# hidrosonico_v0-4.net
KiCad netlist of a schematic drawn in EAGLE
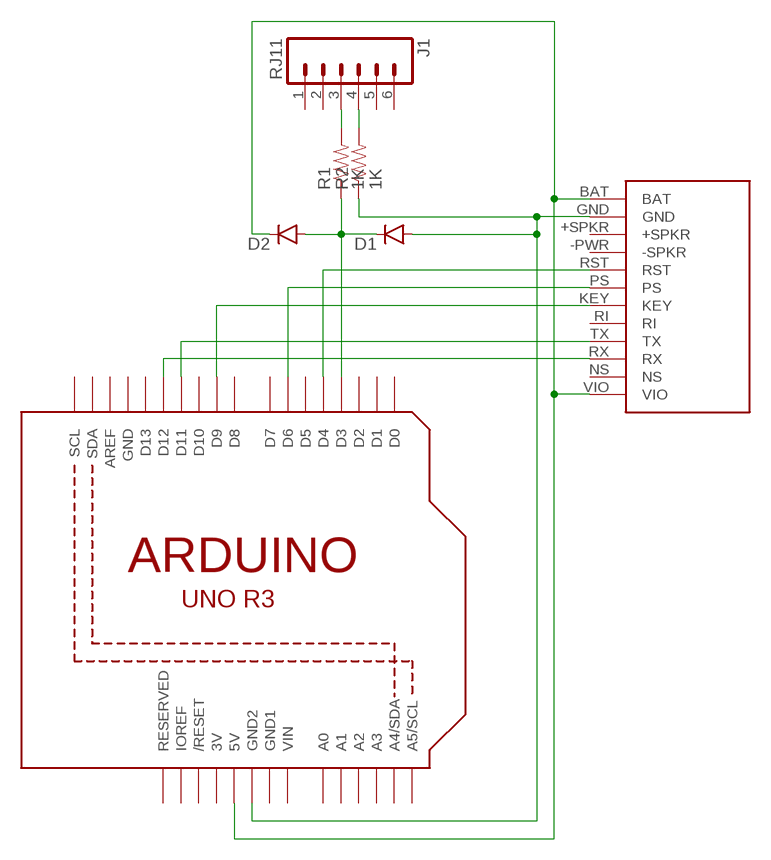
[diagram p0: schematic, sheet 1]

(export (version "E")
  (design (tool "Eeschema 10.0.6"))
  (components
    (comp (ref "D1")
      (value "DIODE1N4148")
      (footprint "eagle-import:DIODE-1N4148")
      (libsource (lib "eagle-import") (part "DIODE1N4148"))
    )
    (comp (ref "D2")
      (value "DIODE1N4148")
      (footprint "eagle-import:DIODE-1N4148")
      (libsource (lib "eagle-import") (part "DIODE1N4148"))
    )
    (comp (ref "J1")
      (value "RJ11")
      (footprint "eagle-import:RJ11-6")
      (libsource (lib "eagle-import") (part "RJ11-6PTH"))
    )
    (comp (ref "R1")
      (value "1K")
      (footprint "eagle-import:AXIAL-0.5")
      (libsource (lib "eagle-import") (part "RESISTORPTH-1/2W"))
    )
    (comp (ref "R2")
      (value "1K")
      (footprint "eagle-import:AXIAL-0.5")
      (libsource (lib "eagle-import") (part "RESISTORPTH-1/2W"))
    )
    (comp (ref "U$1")
      (value "ADAFRUIT_FONA800")
      (footprint "eagle-import:FONA")
      (libsource (lib "eagle-import") (part "ADAFRUIT_FONA800"))
    )
    (comp (ref "U2")
      (value "ARDUINOR3-DIMENSION")
      (footprint "eagle-import:ARDUINOR3")
      (libsource (lib "eagle-import") (part "ARDUINOR3-DIMENSION"))
    )
  )
  (nets
    (net (code "1") (name "/3V") (class "Default")
      (node (ref "U2") (pin "3V") (pinfunction "3V_3V") (pintype "power_in"))
    )
    (net (code "2") (name "/GND") (class "Default")
      (node (ref "U2") (pin "GND") (pinfunction "GND_GND") (pintype "power_in"))
    )
    (net (code "3") (name "/GND1") (class "Default")
      (node (ref "U2") (pin "GND1") (pinfunction "GND1_GND1") (pintype "power_in"))
    )
    (net (code "4") (name "/VIN") (class "Default")
      (node (ref "U2") (pin "VIN") (pinfunction "VIN_VIN") (pintype "power_in"))
    )
    (net (code "5") (name "Net-(D2-PadC)") (class "Default")
      (node (ref "D2") (pin "C") (pinfunction "C_C") (pintype "passive"))
      (node (ref "U$1") (pin "BAT") (pinfunction "BAT_BAT") (pintype "power_in"))
      (node (ref "U$1") (pin "VIO") (pinfunction "VIO_VIO") (pintype "power_in"))
      (node (ref "U2") (pin "5V") (pinfunction "5V_5V") (pintype "power_in"))
    )
    (net (code "6") (name "Net-(R1-1)") (class "Default")
      (node (ref "D1") (pin "C") (pinfunction "C_C") (pintype "passive"))
      (node (ref "D2") (pin "A") (pinfunction "A_A") (pintype "passive"))
      (node (ref "R1") (pin "P$1") (pinfunction "1_P$1") (pintype "passive"))
      (node (ref "U2") (pin "D3") (pinfunction "D3_D3") (pintype "bidirectional"))
    )
    (net (code "7") (name "Net-(R1-2)") (class "Default")
      (node (ref "J1") (pin "3") (pinfunction "3_3") (pintype "passive"))
      (node (ref "R1") (pin "P$2") (pinfunction "2_P$2") (pintype "passive"))
    )
    (net (code "8") (name "Net-(R2-1)") (class "Default")
      (node (ref "D1") (pin "A") (pinfunction "A_A") (pintype "passive"))
      (node (ref "R2") (pin "P$1") (pinfunction "1_P$1") (pintype "passive"))
      (node (ref "U$1") (pin "GND") (pinfunction "GND_GND") (pintype "power_in"))
      (node (ref "U2") (pin "GND2") (pinfunction "GND2_GND2") (pintype "power_in"))
    )
    (net (code "9") (name "Net-(R2-2)") (class "Default")
      (node (ref "J1") (pin "4") (pinfunction "4_4") (pintype "passive"))
      (node (ref "R2") (pin "P$2") (pinfunction "2_P$2") (pintype "passive"))
    )
    (net (code "10") (name "Net-(U$1-PadKEY)") (class "Default")
      (node (ref "U$1") (pin "KEY") (pinfunction "KEY_KEY") (pintype "input"))
      (node (ref "U2") (pin "D9") (pinfunction "D9_D9") (pintype "bidirectional"))
    )
    (net (code "11") (name "Net-(U$1-PadPS)") (class "Default")
      (node (ref "U$1") (pin "PS") (pinfunction "PS_PS") (pintype "output"))
      (node (ref "U2") (pin "D6") (pinfunction "D6_D6") (pintype "bidirectional"))
    )
    (net (code "12") (name "Net-(U$1-PadRST)") (class "Default")
      (node (ref "U$1") (pin "RST") (pinfunction "RST_RST") (pintype "input"))
      (node (ref "U2") (pin "D4") (pinfunction "D4_D4") (pintype "bidirectional"))
    )
    (net (code "13") (name "Net-(U$1-PadRX)") (class "Default")
      (node (ref "U$1") (pin "RX") (pinfunction "RX_RX") (pintype "input"))
      (node (ref "U2") (pin "D12") (pinfunction "D12_D12") (pintype "bidirectional"))
    )
    (net (code "14") (name "Net-(U$1-PadTX)") (class "Default")
      (node (ref "U$1") (pin "TX") (pinfunction "TX_TX") (pintype "output"))
      (node (ref "U2") (pin "D11") (pinfunction "D11_D11") (pintype "bidirectional"))
    )
    (net (code "15") (name "unconnected-(J1-Pad1)") (class "Default")
      (node (ref "J1") (pin "1") (pinfunction "1_1") (pintype "passive"))
    )
    (net (code "16") (name "unconnected-(J1-Pad2)") (class "Default")
      (node (ref "J1") (pin "2") (pinfunction "2_2") (pintype "passive"))
    )
    (net (code "17") (name "unconnected-(J1-Pad5)") (class "Default")
      (node (ref "J1") (pin "5") (pinfunction "5_5") (pintype "passive"))
    )
    (net (code "18") (name "unconnected-(J1-Pad6)") (class "Default")
      (node (ref "J1") (pin "6") (pinfunction "6_6") (pintype "passive"))
    )
    (net (code "19") (name "unconnected-(U$1--SPKR-Pad-PWR)") (class "Default")
      (node (ref "U$1") (pin "-PWR") (pinfunction "-SPKR_-PWR") (pintype "output"))
    )
    (net (code "20") (name "unconnected-(U$1-Pad+SPKR)") (class "Default")
      (node (ref "U$1") (pin "+SPKR") (pinfunction "+SPKR_+SPKR") (pintype "output"))
    )
    (net (code "21") (name "unconnected-(U$1-PadNS)") (class "Default")
      (node (ref "U$1") (pin "NS") (pinfunction "NS_NS") (pintype "output"))
    )
    (net (code "22") (name "unconnected-(U$1-PadRI)") (class "Default")
      (node (ref "U$1") (pin "RI") (pinfunction "RI_RI") (pintype "output"))
    )
    (net (code "23") (name "unconnected-(U2-A4{slash}SDA-PadA4)") (class "Default")
      (node (ref "U2") (pin "A4") (pinfunction "A4/SDA_A4") (pintype "bidirectional"))
    )
    (net (code "24") (name "unconnected-(U2-A5{slash}SCL-PadA5)") (class "Default")
      (node (ref "U2") (pin "A5") (pinfunction "A5/SCL_A5") (pintype "bidirectional"))
    )
    (net (code "25") (name "unconnected-(U2-PadA0)") (class "Default")
      (node (ref "U2") (pin "A0") (pinfunction "A0_A0") (pintype "bidirectional"))
    )
    (net (code "26") (name "unconnected-(U2-PadA1)") (class "Default")
      (node (ref "U2") (pin "A1") (pinfunction "A1_A1") (pintype "bidirectional"))
    )
    (net (code "27") (name "unconnected-(U2-PadA2)") (class "Default")
      (node (ref "U2") (pin "A2") (pinfunction "A2_A2") (pintype "bidirectional"))
    )
    (net (code "28") (name "unconnected-(U2-PadA3)") (class "Default")
      (node (ref "U2") (pin "A3") (pinfunction "A3_A3") (pintype "bidirectional"))
    )
    (net (code "29") (name "unconnected-(U2-PadAREF)") (class "Default")
      (node (ref "U2") (pin "AREF") (pinfunction "AREF_AREF") (pintype "bidirectional"))
    )
    (net (code "30") (name "unconnected-(U2-PadD0)") (class "Default")
      (node (ref "U2") (pin "D0") (pinfunction "D0_D0") (pintype "bidirectional"))
    )
    (net (code "31") (name "unconnected-(U2-PadD1)") (class "Default")
      (node (ref "U2") (pin "D1") (pinfunction "D1_D1") (pintype "bidirectional"))
    )
    (net (code "32") (name "unconnected-(U2-PadD2)") (class "Default")
      (node (ref "U2") (pin "D2") (pinfunction "D2_D2") (pintype "bidirectional"))
    )
    (net (code "33") (name "unconnected-(U2-PadD5)") (class "Default")
      (node (ref "U2") (pin "D5") (pinfunction "D5_D5") (pintype "bidirectional"))
    )
    (net (code "34") (name "unconnected-(U2-PadD7)") (class "Default")
      (node (ref "U2") (pin "D7") (pinfunction "D7_D7") (pintype "bidirectional"))
    )
    (net (code "35") (name "unconnected-(U2-PadD8)") (class "Default")
      (node (ref "U2") (pin "D8") (pinfunction "D8_D8") (pintype "bidirectional"))
    )
    (net (code "36") (name "unconnected-(U2-PadD10)") (class "Default")
      (node (ref "U2") (pin "D10") (pinfunction "D10_D10") (pintype "bidirectional"))
    )
    (net (code "37") (name "unconnected-(U2-PadD13)") (class "Default")
      (node (ref "U2") (pin "D13") (pinfunction "D13_D13") (pintype "bidirectional"))
    )
    (net (code "38") (name "unconnected-(U2-PadIOREF)") (class "Default")
      (node (ref "U2") (pin "IOREF") (pinfunction "IOREF_IOREF") (pintype "output"))
    )
    (net (code "39") (name "unconnected-(U2-PadRESERVED)") (class "Default")
      (node (ref "U2") (pin "RESERVED") (pinfunction "RESERVED_RESERVED") (pintype "no_connect"))
    )
    (net (code "40") (name "unconnected-(U2-PadSCL)") (class "Default")
      (node (ref "U2") (pin "SCL") (pinfunction "SCL_SCL") (pintype "bidirectional"))
    )
    (net (code "41") (name "unconnected-(U2-PadSDA)") (class "Default")
      (node (ref "U2") (pin "SDA") (pinfunction "SDA_SDA") (pintype "bidirectional"))
    )
    (net (code "42") (name "unconnected-(U2-{slash}RESET-PadRESET)") (class "Default")
      (node (ref "U2") (pin "RESET") (pinfunction "/RESET_RESET") (pintype "bidirectional"))
    )
  )
)
